# BusPirate-ultra-proto-adj_vreg_v_0.net
KiCad netlist of a schematic drawn in EAGLE
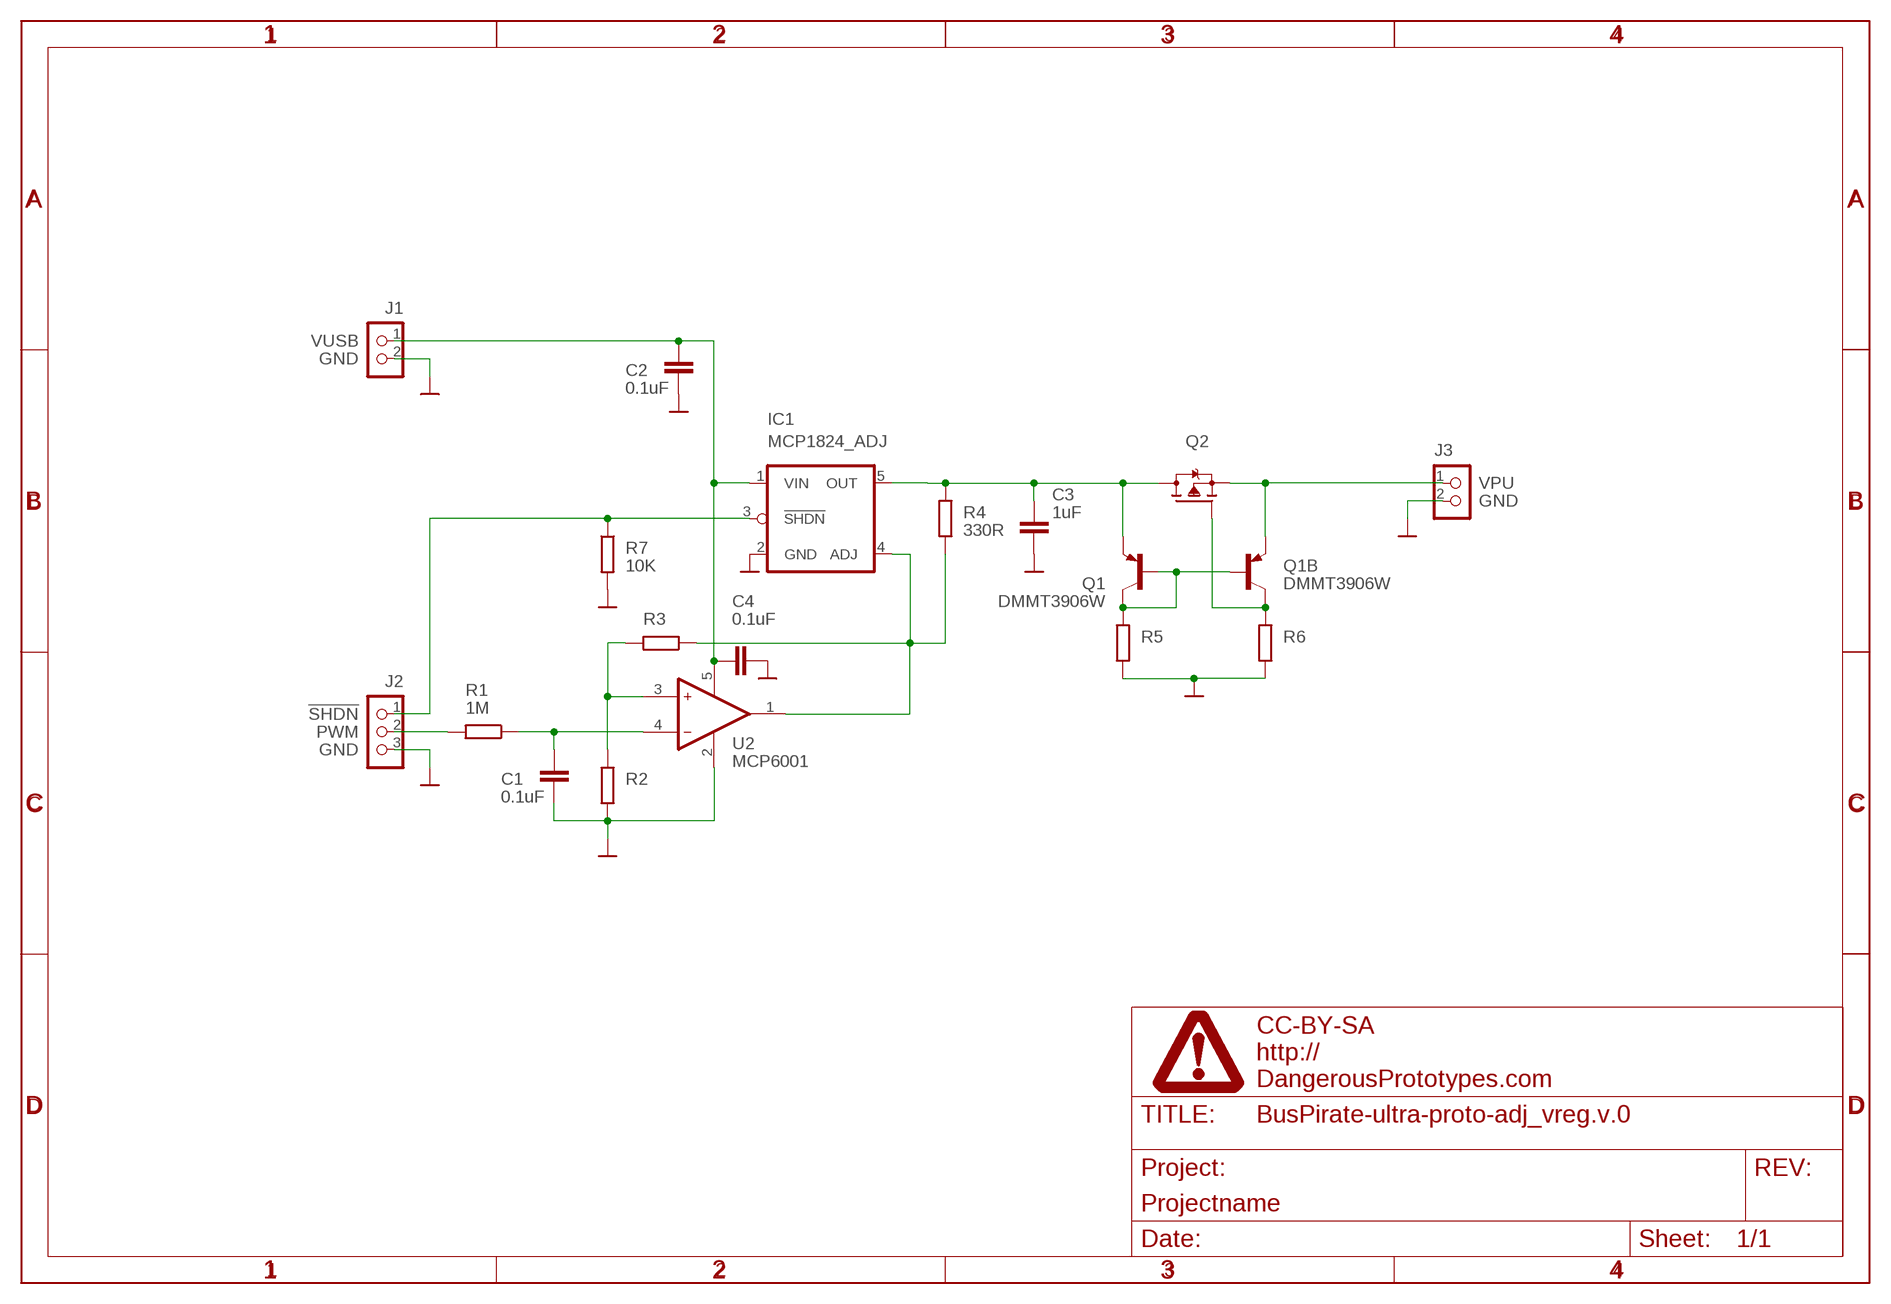
[diagram p0: schematic, sheet 1]

(export (version "E")
  (design (tool "Eeschema 10.0.6"))
  (components
    (comp (ref "C1")
      (value "0.1uF")
      (footprint "eagle-import:C603")
      (libsource (lib "eagle-import") (part "CAPACITOR_NPOL-0603"))
    )
    (comp (ref "C2")
      (value "0.1uF")
      (footprint "eagle-import:C603")
      (libsource (lib "eagle-import") (part "CAPACITOR_NPOL-0603"))
    )
    (comp (ref "C3")
      (value "1uF")
      (footprint "eagle-import:C603")
      (libsource (lib "eagle-import") (part "CAPACITOR_NPOL-0603"))
    )
    (comp (ref "C4")
      (value "0.1uF")
      (footprint "eagle-import:C603")
      (libsource (lib "eagle-import") (part "CAPACITOR_NPOL-0603"))
    )
    (comp (ref "IC1")
      (value "MCP1824_ADJ")
      (footprint "eagle-import:SOT-23-5")
      (libsource (lib "eagle-import") (part "IC_MCP1824_ADJ"))
    )
    (comp (ref "J1")
      (value "CON_HEADER_1X02-PTH")
      (footprint "eagle-import:M1X2")
      (libsource (lib "eagle-import") (part "CON_HEADER_1X02-PTH"))
    )
    (comp (ref "J2")
      (value "CON_HEADER_1X03-PTH")
      (footprint "eagle-import:M1X3")
      (libsource (lib "eagle-import") (part "CON_HEADER_1X03-PTH"))
    )
    (comp (ref "J3")
      (value "CON_HEADER_1X02-PTH")
      (footprint "eagle-import:M1X2")
      (libsource (lib "eagle-import") (part "CON_HEADER_1X02-PTH"))
    )
    (comp (ref "PAGE1")
      (value "FRAME_DINA4_L")
      (footprint "eagle-import:DP_LOGO")
      (libsource (lib "eagle-import") (part "FRAME_DINA4_L"))
    )
    (comp (ref "Q1")
      (value "DMMT3906W")
      (footprint "eagle-import:SOT-363")
      (libsource (lib "eagle-import") (part "TRANSISTOR-BJT_DMMT3906W"))
    )
    (comp (ref "Q2")
      (value "TRANSISTOR_FET_TSM2301CX")
      (footprint "eagle-import:SOT-23")
      (libsource (lib "eagle-import") (part "TRANSISTOR_FET_TSM2301CX"))
    )
    (comp (ref "R1")
      (value "1M")
      (footprint "eagle-import:R603")
      (libsource (lib "eagle-import") (part "RESISTOR-0603"))
    )
    (comp (ref "R2")
      (value "RESISTOR-0603")
      (footprint "eagle-import:R603")
      (libsource (lib "eagle-import") (part "RESISTOR-0603"))
    )
    (comp (ref "R3")
      (value "RESISTOR-0603")
      (footprint "eagle-import:R603")
      (libsource (lib "eagle-import") (part "RESISTOR-0603"))
    )
    (comp (ref "R4")
      (value "330R")
      (footprint "eagle-import:R603")
      (libsource (lib "eagle-import") (part "RESISTOR-0603"))
    )
    (comp (ref "R5")
      (value "RESISTOR-0603")
      (footprint "eagle-import:R603")
      (libsource (lib "eagle-import") (part "RESISTOR-0603"))
    )
    (comp (ref "R6")
      (value "RESISTOR-0603")
      (footprint "eagle-import:R603")
      (libsource (lib "eagle-import") (part "RESISTOR-0603"))
    )
    (comp (ref "R7")
      (value "10K")
      (footprint "eagle-import:R603")
      (libsource (lib "eagle-import") (part "RESISTOR-0603"))
    )
    (comp (ref "U2")
      (value "MCP6001")
      (footprint "eagle-import:SOT-23-5")
      (libsource (lib "eagle-import") (part "IC_OP-AMP_MCP6001"))
    )
  )
  (nets
    (net (code "1") (name "/PWM") (class "Default")
      (node (ref "J2") (pin "2") (pinfunction "2_2") (pintype "bidirectional"))
      (node (ref "R1") (pin "2") (pinfunction "2_2") (pintype "passive"))
    )
    (net (code "2") (name "/VPU") (class "Default")
      (node (ref "J3") (pin "1") (pinfunction "1_1") (pintype "passive"))
      (node (ref "Q1") (pin "5") (pinfunction "E_5") (pintype "passive"))
      (node (ref "Q2") (pin "2") (pinfunction "S_2") (pintype "passive"))
    )
    (net (code "3") (name "/VUSB") (class "Default")
      (node (ref "C2") (pin "1") (pinfunction "1_1") (pintype "passive"))
      (node (ref "C4") (pin "1") (pinfunction "1_1") (pintype "passive"))
      (node (ref "IC1") (pin "1") (pinfunction "VIN_1") (pintype "input"))
      (node (ref "J1") (pin "1") (pinfunction "1_1") (pintype "passive"))
      (node (ref "U2") (pin "5") (pinfunction "V+_5") (pintype "power_in"))
    )
    (net (code "4") (name "/~{SHDN}") (class "Default")
      (node (ref "IC1") (pin "3") (pinfunction "~{SHDN}_3") (pintype "input"))
      (node (ref "J2") (pin "1") (pinfunction "1_1") (pintype "bidirectional"))
      (node (ref "R7") (pin "1") (pinfunction "1_1") (pintype "passive"))
    )
    (net (code "5") (name "Net-(IC1-ADJ)") (class "Default")
      (node (ref "IC1") (pin "4") (pinfunction "ADJ_4") (pintype "input"))
      (node (ref "R3") (pin "1") (pinfunction "1_1") (pintype "passive"))
      (node (ref "R4") (pin "1") (pinfunction "1_1") (pintype "passive"))
      (node (ref "U2") (pin "1") (pinfunction "OUT_1") (pintype "output"))
    )
    (net (code "6") (name "Net-(IC1-OUT)") (class "Default")
      (node (ref "C3") (pin "1") (pinfunction "1_1") (pintype "passive"))
      (node (ref "IC1") (pin "5") (pinfunction "OUT_5") (pintype "output"))
      (node (ref "Q1") (pin "4") (pinfunction "E_4") (pintype "passive"))
      (node (ref "Q2") (pin "3") (pinfunction "D_3") (pintype "passive"))
      (node (ref "R4") (pin "2") (pinfunction "2_2") (pintype "passive"))
    )
    (net (code "7") (name "Net-(Q1A-B)") (class "Default")
      (node (ref "Q1") (pin "1") (pinfunction "B_1") (pintype "passive"))
      (node (ref "Q1") (pin "2") (pinfunction "B_2") (pintype "passive"))
      (node (ref "Q1") (pin "3") (pinfunction "C_3") (pintype "passive"))
      (node (ref "R5") (pin "2") (pinfunction "2_2") (pintype "passive"))
    )
    (net (code "8") (name "Net-(Q1B-C)") (class "Default")
      (node (ref "Q1") (pin "6") (pinfunction "C_6") (pintype "passive"))
      (node (ref "Q2") (pin "1") (pinfunction "G_1") (pintype "passive"))
      (node (ref "R6") (pin "2") (pinfunction "2_2") (pintype "passive"))
    )
    (net (code "9") (name "Net-(U2-+)") (class "Default")
      (node (ref "R2") (pin "1") (pinfunction "1_1") (pintype "passive"))
      (node (ref "R3") (pin "2") (pinfunction "2_2") (pintype "passive"))
      (node (ref "U2") (pin "3") (pinfunction "+_3") (pintype "input"))
    )
    (net (code "10") (name "Net-(U2--)") (class "Default")
      (node (ref "C1") (pin "1") (pinfunction "1_1") (pintype "passive"))
      (node (ref "R1") (pin "1") (pinfunction "1_1") (pintype "passive"))
      (node (ref "U2") (pin "4") (pinfunction "-_4") (pintype "input"))
    )
    (net (code "11") (name "SUPPLY_GND") (class "Default")
      (node (ref "C1") (pin "2") (pinfunction "2_2") (pintype "passive"))
      (node (ref "C2") (pin "2") (pinfunction "2_2") (pintype "passive"))
      (node (ref "C3") (pin "2") (pinfunction "2_2") (pintype "passive"))
      (node (ref "C4") (pin "2") (pinfunction "2_2") (pintype "passive"))
      (node (ref "IC1") (pin "2") (pinfunction "GND_2") (pintype "power_in"))
      (node (ref "J1") (pin "2") (pinfunction "2_2") (pintype "passive"))
      (node (ref "J2") (pin "3") (pinfunction "3_3") (pintype "bidirectional"))
      (node (ref "J3") (pin "2") (pinfunction "2_2") (pintype "passive"))
      (node (ref "R2") (pin "2") (pinfunction "2_2") (pintype "passive"))
      (node (ref "R5") (pin "1") (pinfunction "1_1") (pintype "passive"))
      (node (ref "R6") (pin "1") (pinfunction "1_1") (pintype "passive"))
      (node (ref "R7") (pin "2") (pinfunction "2_2") (pintype "passive"))
      (node (ref "U2") (pin "2") (pinfunction "V-_2") (pintype "power_in"))
    )
  )
)
